# SCH_EsquematicoCorregido_Final.net
KiCad netlist of a schematic drawn in EasyEDA
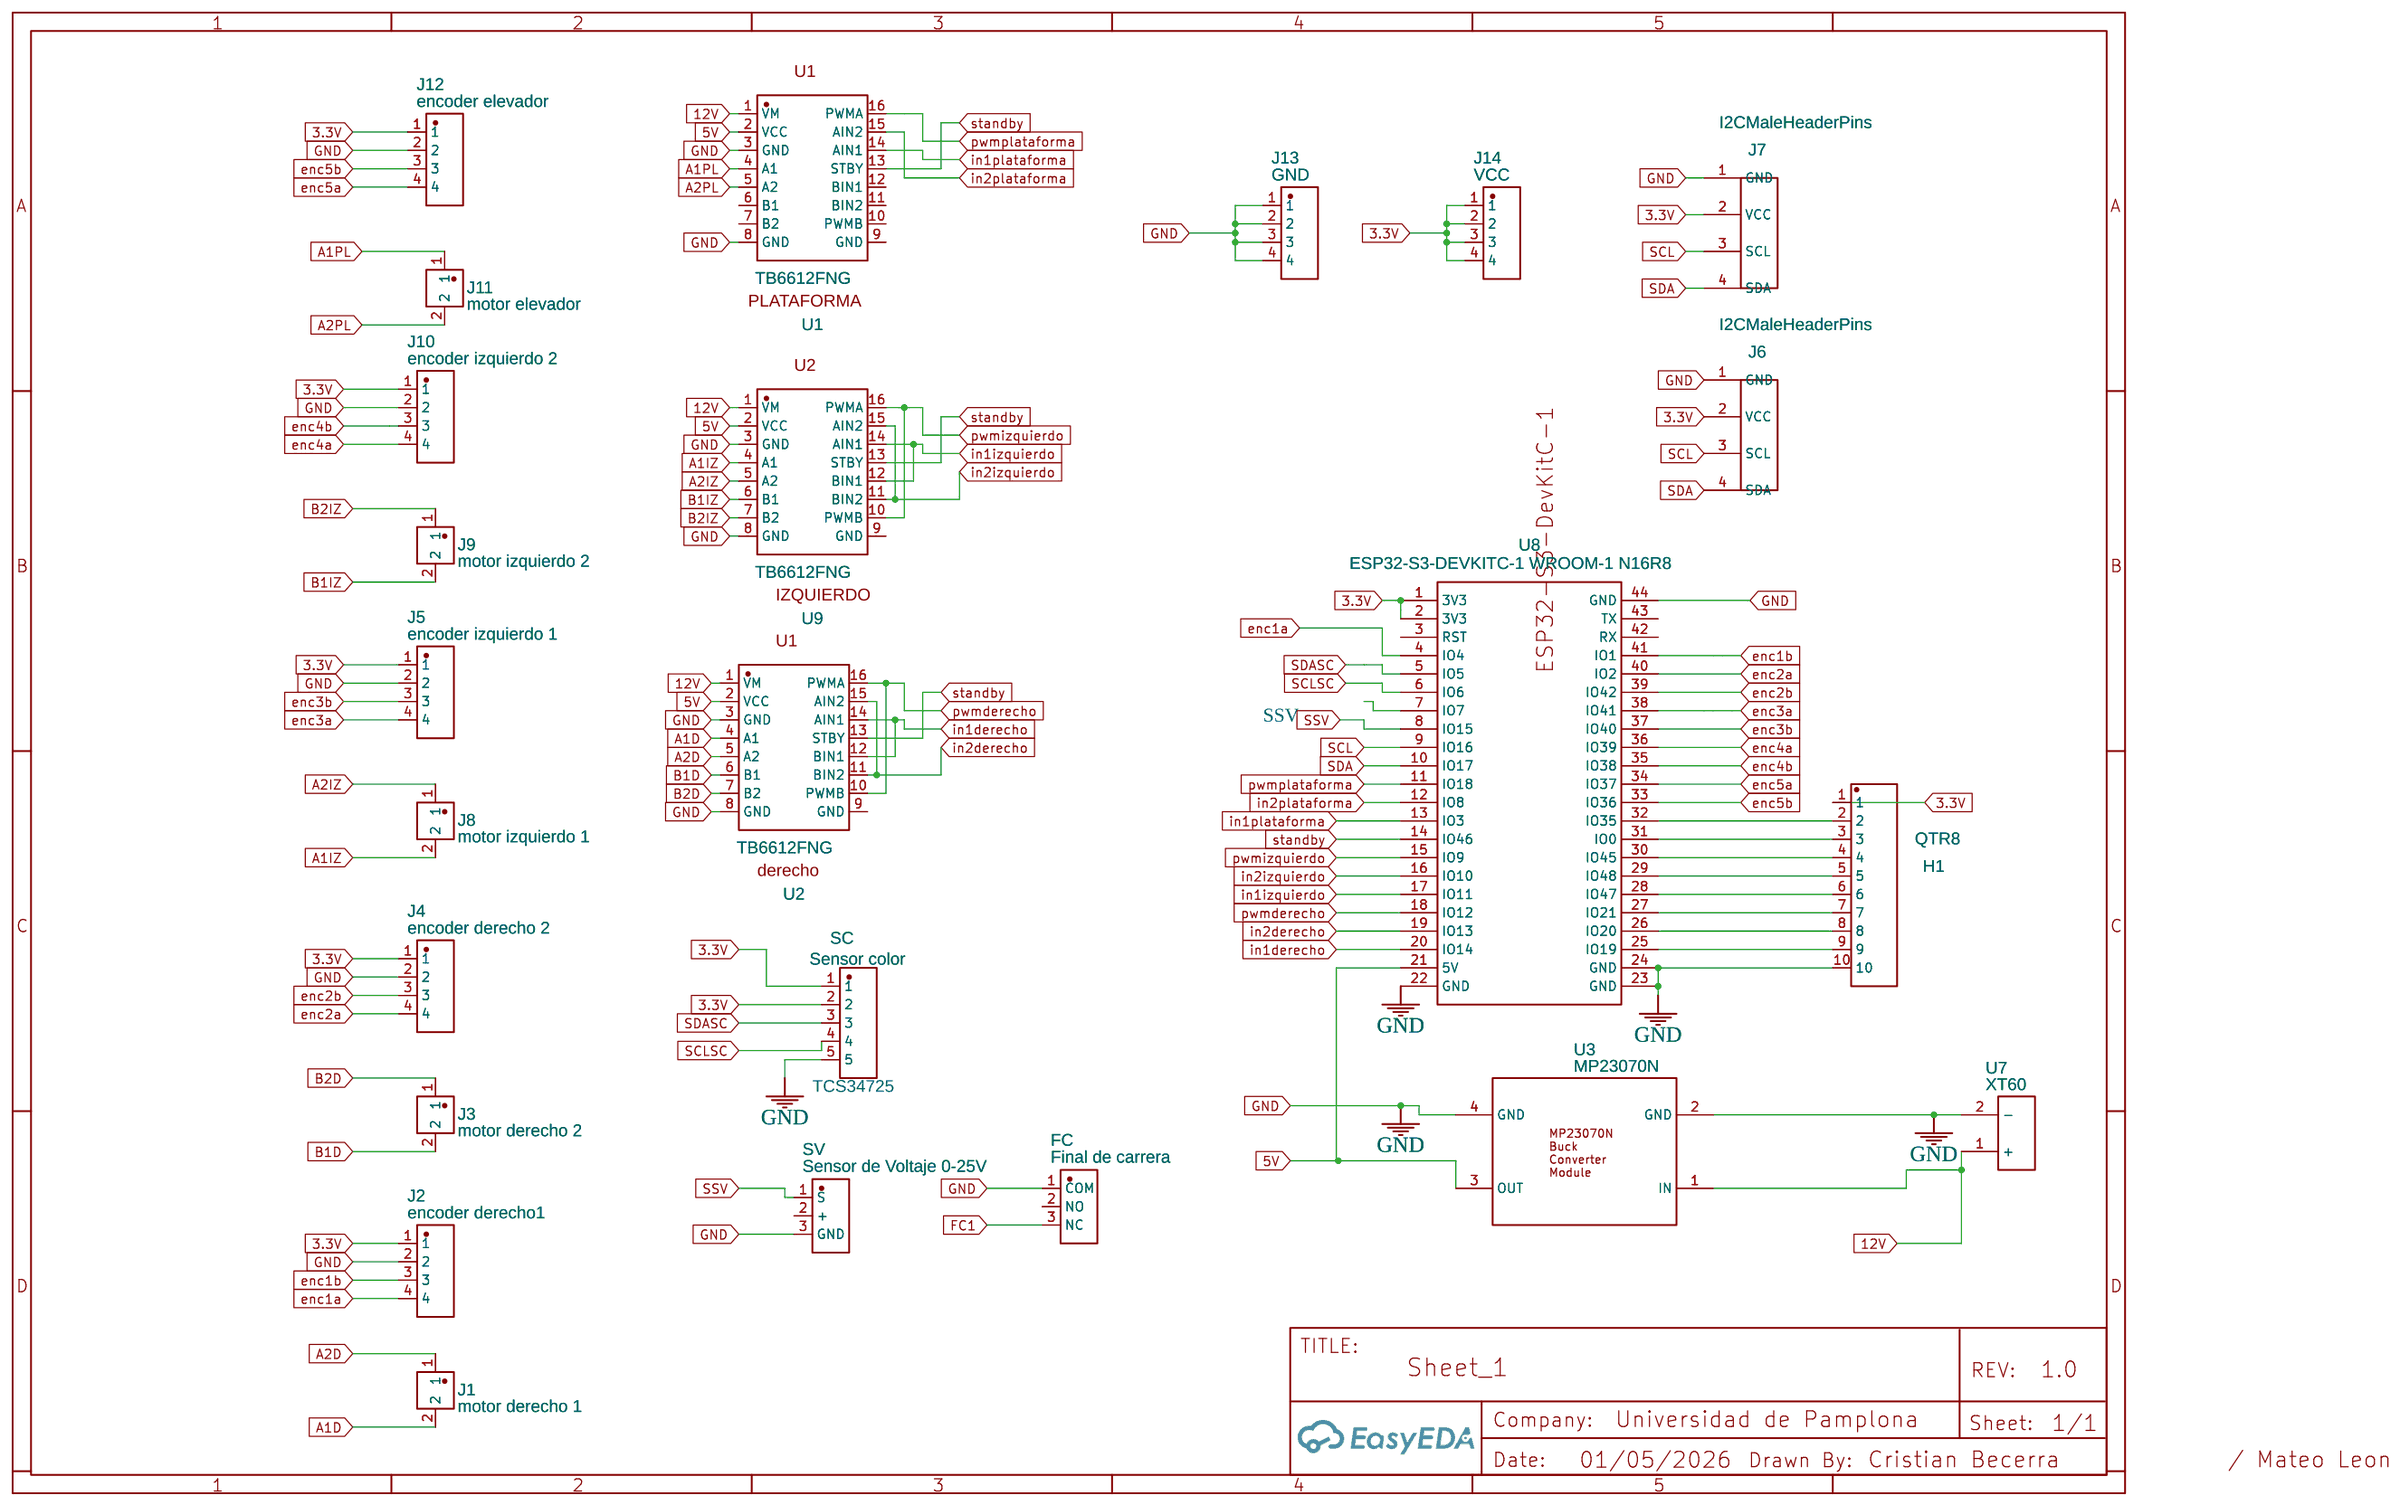
[diagram p0: schematic sheet]

(export (version "E")
  (design (tool "Eeschema 10.0.6"))
  (components
    (comp (ref "FC")
      (value "Final de carrera")
      (fields
        (field (name "Manufacturer Part") "5557WRF-1X3P(HDGC4201WR-F-1X3P)")
        (field (name "Manufacturer") "HDGC(华德共创)")
      )
      (libsource (lib "") (part "5557WRF-1X3P(HDGC4201WR-F-1X3P)"))
    )
    (comp (ref "H1")
      (value "QTR8")
      (fields (field (name "Manufacturer Part") "2.54-1*10P针") (field (name "Manufacturer") "BOOMELE(博穆精密)"))
      (libsource (lib "") (part "Header-Male-2.54_1x10"))
    )
    (comp (ref "J1")
      (value "motor derecho 1")
      (fields (field (name "Manufacturer Part") "2.54*2P-P=2.54mm"))
      (libsource (lib "") (part "2.54*2P-P=2.54MM"))
    )
    (comp (ref "J2")
      (value "encoder derecho1")
      (fields (field (name "Manufacturer Part") "38001334") (field (name "Manufacturer") "MOLEX"))
      (libsource (lib "") (part "38001334"))
    )
    (comp (ref "J3")
      (value "motor derecho 2")
      (fields (field (name "Manufacturer Part") "2.54*2P-P=2.54mm"))
      (libsource (lib "") (part "2.54*2P-P=2.54MM"))
    )
    (comp (ref "J4")
      (value "encoder derecho 2")
      (fields (field (name "Manufacturer Part") "38001334") (field (name "Manufacturer") "MOLEX"))
      (libsource (lib "") (part "38001334"))
    )
    (comp (ref "J5")
      (value "encoder izquierdo 1")
      (fields (field (name "Manufacturer Part") "38001334") (field (name "Manufacturer") "MOLEX"))
      (libsource (lib "") (part "38001334"))
    )
    (comp (ref "J6") (value "I2CMaleHeaderPins") (libsource (lib "") (part "I2CMaleHeaderPins")))
    (comp (ref "J7") (value "I2CMaleHeaderPins") (libsource (lib "") (part "I2CMaleHeaderPins")))
    (comp (ref "J8")
      (value "motor izquierdo 1")
      (fields (field (name "Manufacturer Part") "2.54*2P-P=2.54mm"))
      (libsource (lib "") (part "2.54*2P-P=2.54MM"))
    )
    (comp (ref "J9")
      (value "motor izquierdo 2")
      (fields (field (name "Manufacturer Part") "2.54*2P-P=2.54mm"))
      (libsource (lib "") (part "2.54*2P-P=2.54MM"))
    )
    (comp (ref "J10")
      (value "encoder izquierdo 2")
      (fields (field (name "Manufacturer Part") "38001334") (field (name "Manufacturer") "MOLEX"))
      (libsource (lib "") (part "38001334"))
    )
    (comp (ref "J11")
      (value "motor elevador")
      (fields (field (name "Manufacturer Part") "2.54*2P-P=2.54mm"))
      (libsource (lib "") (part "2.54*2P-P=2.54MM"))
    )
    (comp (ref "J12")
      (value "encoder elevador")
      (fields (field (name "Manufacturer Part") "38001334") (field (name "Manufacturer") "MOLEX"))
      (libsource (lib "") (part "38001334"))
    )
    (comp (ref "J13")
      (value "GND")
      (fields (field (name "Manufacturer Part") "38001334") (field (name "Manufacturer") "MOLEX"))
      (libsource (lib "") (part "38001334"))
    )
    (comp (ref "J14")
      (value "VCC")
      (fields (field (name "Manufacturer Part") "38001334") (field (name "Manufacturer") "MOLEX"))
      (libsource (lib "") (part "38001334"))
    )
    (comp (ref "SC")
      (value "Sensor color")
      (fields
        (field (name "Manufacturer Part") "5557WR-1X5P(HDGC4201WR-1X5P)")
        (field (name "Manufacturer") "HDGC(华德共创)")
      )
      (libsource (lib "") (part "5557WR-1X5P(HDGC4201WR-1X5P)"))
    )
    (comp (ref "SV")
      (value "Sensor de Voltaje 0-25V")
      (fields
        (field (name "Manufacturer Part") "5557WRF-1X3P(HDGC4201WR-F-1X3P)")
        (field (name "Manufacturer") "HDGC(华德共创)")
      )
      (libsource (lib "") (part "5557WRF-1X3P(HDGC4201WR-F-1X3P)_1"))
    )
    (comp (ref "U1") (value "TB6612FNG") (libsource (lib "") (part "TB6612FNG SPARKFUN_1")))
    (comp (ref "U2") (value "TB6612FNG") (libsource (lib "") (part "TB6612FNG SPARKFUN_2")))
    (comp (ref "U3")
      (value "MP23070N")
      (fields (field (name "Manufacturer Part") "MP23070N Buck Converter Module"))
      (libsource (lib "") (part "MP23070N BUCK CONVERTER MODULE"))
    )
    (comp (ref "U7") (value "XT60") (libsource (lib "") (part "XT60")))
    (comp (ref "U8")
      (value "ESP32-S3-DEVKITC-1 WROOM-1 N16R8")
      (fields (field (name "Manufacturer") "Espressif"))
      (libsource (lib "") (part "ESP32-S3-DEVKITC-1 WROOM-1 N16R8"))
    )
    (comp (ref "U9") (value "TB6612FNG") (libsource (lib "") (part "TB6612FNG SPARKFUN")))
  )
  (nets
    (net (code "1") (name "3.3V") (class "Default")
      (node (ref "H1") (pin "1") (pinfunction "1_1") (pintype "unspecified"))
      (node (ref "J10") (pin "1") (pinfunction "1_1") (pintype "unspecified"))
      (node (ref "J12") (pin "1") (pinfunction "1_1") (pintype "unspecified"))
      (node (ref "J14") (pin "1") (pinfunction "1_1") (pintype "unspecified"))
      (node (ref "J14") (pin "2") (pinfunction "2_2") (pintype "unspecified"))
      (node (ref "J14") (pin "3") (pinfunction "3_3") (pintype "unspecified"))
      (node (ref "J14") (pin "4") (pinfunction "4_4") (pintype "unspecified"))
      (node (ref "J2") (pin "1") (pinfunction "1_1") (pintype "unspecified"))
      (node (ref "J4") (pin "1") (pinfunction "1_1") (pintype "unspecified"))
      (node (ref "J5") (pin "1") (pinfunction "1_1") (pintype "unspecified"))
      (node (ref "J6") (pin "2") (pinfunction "VCC_2") (pintype "unspecified"))
      (node (ref "J7") (pin "2") (pinfunction "VCC_2") (pintype "unspecified"))
      (node (ref "SC") (pin "1") (pinfunction "1_1") (pintype "unspecified"))
      (node (ref "SC") (pin "2") (pinfunction "2_2") (pintype "unspecified"))
      (node (ref "U8") (pin "1") (pinfunction "3V3_1") (pintype "unspecified"))
      (node (ref "U8") (pin "2") (pinfunction "3V3_2") (pintype "unspecified"))
    )
    (net (code "2") (name "5V") (class "Default")
      (node (ref "U1") (pin "2") (pinfunction "VCC_2") (pintype "unspecified"))
      (node (ref "U2") (pin "2") (pinfunction "VCC_2") (pintype "unspecified"))
      (node (ref "U3") (pin "3") (pinfunction "OUT_3") (pintype "unspecified"))
      (node (ref "U8") (pin "21") (pinfunction "5V_21") (pintype "unspecified"))
      (node (ref "U9") (pin "2") (pinfunction "VCC_2") (pintype "unspecified"))
    )
    (net (code "3") (name "12V") (class "Default")
      (node (ref "U1") (pin "1") (pinfunction "VM_1") (pintype "unspecified"))
      (node (ref "U2") (pin "1") (pinfunction "VM_1") (pintype "unspecified"))
      (node (ref "U3") (pin "1") (pinfunction "IN_1") (pintype "unspecified"))
      (node (ref "U7") (pin "1") (pinfunction "+_1") (pintype "unspecified"))
      (node (ref "U9") (pin "1") (pinfunction "VM_1") (pintype "unspecified"))
    )
    (net (code "4") (name "A1D") (class "Default")
      (node (ref "J1") (pin "2") (pinfunction "2_2") (pintype "unspecified"))
      (node (ref "U2") (pin "4") (pinfunction "A1_4") (pintype "unspecified"))
    )
    (net (code "5") (name "A1IZ") (class "Default")
      (node (ref "J8") (pin "2") (pinfunction "2_2") (pintype "unspecified"))
      (node (ref "U9") (pin "4") (pinfunction "A1_4") (pintype "unspecified"))
    )
    (net (code "6") (name "A1PL") (class "Default")
      (node (ref "J11") (pin "1") (pinfunction "1_1") (pintype "unspecified"))
      (node (ref "U1") (pin "4") (pinfunction "A1_4") (pintype "unspecified"))
    )
    (net (code "7") (name "A2D") (class "Default")
      (node (ref "J1") (pin "1") (pinfunction "1_1") (pintype "unspecified"))
      (node (ref "U2") (pin "5") (pinfunction "A2_5") (pintype "unspecified"))
    )
    (net (code "8") (name "A2IZ") (class "Default")
      (node (ref "J8") (pin "1") (pinfunction "1_1") (pintype "unspecified"))
      (node (ref "U9") (pin "5") (pinfunction "A2_5") (pintype "unspecified"))
    )
    (net (code "9") (name "A2PL") (class "Default")
      (node (ref "J11") (pin "2") (pinfunction "2_2") (pintype "unspecified"))
      (node (ref "U1") (pin "5") (pinfunction "A2_5") (pintype "unspecified"))
    )
    (net (code "10") (name "B1D") (class "Default")
      (node (ref "J3") (pin "2") (pinfunction "2_2") (pintype "unspecified"))
      (node (ref "U2") (pin "6") (pinfunction "B1_6") (pintype "unspecified"))
    )
    (net (code "11") (name "B1IZ") (class "Default")
      (node (ref "J9") (pin "2") (pinfunction "2_2") (pintype "unspecified"))
      (node (ref "U9") (pin "6") (pinfunction "B1_6") (pintype "unspecified"))
    )
    (net (code "12") (name "B2D") (class "Default")
      (node (ref "J3") (pin "1") (pinfunction "1_1") (pintype "unspecified"))
      (node (ref "U2") (pin "7") (pinfunction "B2_7") (pintype "unspecified"))
    )
    (net (code "13") (name "B2IZ") (class "Default")
      (node (ref "J9") (pin "1") (pinfunction "1_1") (pintype "unspecified"))
      (node (ref "U9") (pin "7") (pinfunction "B2_7") (pintype "unspecified"))
    )
    (net (code "14") (name "FC1") (class "Default")
      (node (ref "FC") (pin "3") (pinfunction "NC_3") (pintype "unspecified"))
    )
    (net (code "15") (name "GND") (class "Default")
      (node (ref "FC") (pin "1") (pinfunction "COM_1") (pintype "unspecified"))
      (node (ref "H1") (pin "10") (pinfunction "10_10") (pintype "unspecified"))
      (node (ref "J10") (pin "2") (pinfunction "2_2") (pintype "unspecified"))
      (node (ref "J12") (pin "2") (pinfunction "2_2") (pintype "unspecified"))
      (node (ref "J13") (pin "1") (pinfunction "1_1") (pintype "unspecified"))
      (node (ref "J13") (pin "2") (pinfunction "2_2") (pintype "unspecified"))
      (node (ref "J13") (pin "3") (pinfunction "3_3") (pintype "unspecified"))
      (node (ref "J13") (pin "4") (pinfunction "4_4") (pintype "unspecified"))
      (node (ref "J2") (pin "2") (pinfunction "2_2") (pintype "unspecified"))
      (node (ref "J4") (pin "2") (pinfunction "2_2") (pintype "unspecified"))
      (node (ref "J5") (pin "2") (pinfunction "2_2") (pintype "unspecified"))
      (node (ref "J6") (pin "1") (pinfunction "GND_1") (pintype "unspecified"))
      (node (ref "J7") (pin "1") (pinfunction "GND_1") (pintype "unspecified"))
      (node (ref "SC") (pin "5") (pinfunction "5_5") (pintype "unspecified"))
      (node (ref "SV") (pin "3") (pinfunction "GND_3") (pintype "unspecified"))
      (node (ref "U1") (pin "3") (pinfunction "GND_3") (pintype "unspecified"))
      (node (ref "U1") (pin "8") (pinfunction "GND_8") (pintype "unspecified"))
      (node (ref "U2") (pin "3") (pinfunction "GND_3") (pintype "unspecified"))
      (node (ref "U2") (pin "8") (pinfunction "GND_8") (pintype "unspecified"))
      (node (ref "U3") (pin "2") (pinfunction "GND_2") (pintype "unspecified"))
      (node (ref "U3") (pin "4") (pinfunction "GND_4") (pintype "unspecified"))
      (node (ref "U7") (pin "2") (pinfunction "-_2") (pintype "unspecified"))
      (node (ref "U8") (pin "22") (pinfunction "GND_22") (pintype "unspecified"))
      (node (ref "U8") (pin "23") (pinfunction "GND_23") (pintype "unspecified"))
      (node (ref "U8") (pin "24") (pinfunction "GND_24") (pintype "unspecified"))
      (node (ref "U8") (pin "44") (pinfunction "GND_44") (pintype "unspecified"))
      (node (ref "U9") (pin "3") (pinfunction "GND_3") (pintype "unspecified"))
      (node (ref "U9") (pin "8") (pinfunction "GND_8") (pintype "unspecified"))
    )
    (net (code "16") (name "Net-(U8-IO0)") (class "Default")
      (node (ref "H1") (pin "3") (pinfunction "3_3") (pintype "unspecified"))
      (node (ref "U8") (pin "31") (pinfunction "IO0_31") (pintype "unspecified"))
    )
    (net (code "17") (name "Net-(U8-IO19)") (class "Default")
      (node (ref "H1") (pin "9") (pinfunction "9_9") (pintype "unspecified"))
      (node (ref "U8") (pin "25") (pinfunction "IO19_25") (pintype "unspecified"))
    )
    (net (code "18") (name "Net-(U8-IO20)") (class "Default")
      (node (ref "H1") (pin "8") (pinfunction "8_8") (pintype "unspecified"))
      (node (ref "U8") (pin "26") (pinfunction "IO20_26") (pintype "unspecified"))
    )
    (net (code "19") (name "Net-(U8-IO21)") (class "Default")
      (node (ref "H1") (pin "7") (pinfunction "7_7") (pintype "unspecified"))
      (node (ref "U8") (pin "27") (pinfunction "IO21_27") (pintype "unspecified"))
    )
    (net (code "20") (name "Net-(U8-IO35)") (class "Default")
      (node (ref "H1") (pin "2") (pinfunction "2_2") (pintype "unspecified"))
      (node (ref "U8") (pin "32") (pinfunction "IO35_32") (pintype "unspecified"))
    )
    (net (code "21") (name "Net-(U8-IO45)") (class "Default")
      (node (ref "H1") (pin "4") (pinfunction "4_4") (pintype "unspecified"))
      (node (ref "U8") (pin "30") (pinfunction "IO45_30") (pintype "unspecified"))
    )
    (net (code "22") (name "Net-(U8-IO47)") (class "Default")
      (node (ref "H1") (pin "6") (pinfunction "6_6") (pintype "unspecified"))
      (node (ref "U8") (pin "28") (pinfunction "IO47_28") (pintype "unspecified"))
    )
    (net (code "23") (name "Net-(U8-IO48)") (class "Default")
      (node (ref "H1") (pin "5") (pinfunction "5_5") (pintype "unspecified"))
      (node (ref "U8") (pin "29") (pinfunction "IO48_29") (pintype "unspecified"))
    )
    (net (code "24") (name "SCL") (class "Default")
      (node (ref "J6") (pin "3") (pinfunction "SCL_3") (pintype "unspecified"))
      (node (ref "J7") (pin "3") (pinfunction "SCL_3") (pintype "unspecified"))
      (node (ref "U8") (pin "9") (pinfunction "IO16_9") (pintype "unspecified"))
    )
    (net (code "25") (name "SCLSC") (class "Default")
      (node (ref "SC") (pin "4") (pinfunction "4_4") (pintype "unspecified"))
      (node (ref "U8") (pin "6") (pinfunction "IO6_6") (pintype "unspecified"))
    )
    (net (code "26") (name "SDA") (class "Default")
      (node (ref "J6") (pin "4") (pinfunction "SDA_4") (pintype "unspecified"))
      (node (ref "J7") (pin "4") (pinfunction "SDA_4") (pintype "unspecified"))
      (node (ref "U8") (pin "10") (pinfunction "IO17_10") (pintype "unspecified"))
    )
    (net (code "27") (name "SDASC") (class "Default")
      (node (ref "SC") (pin "3") (pinfunction "3_3") (pintype "unspecified"))
      (node (ref "U8") (pin "5") (pinfunction "IO5_5") (pintype "unspecified"))
    )
    (net (code "28") (name "SSV") (class "Default")
      (node (ref "SV") (pin "1") (pinfunction "S_1") (pintype "unspecified"))
      (node (ref "U8") (pin "8") (pinfunction "IO15_8") (pintype "unspecified"))
    )
    (net (code "29") (name "enc1a") (class "Default")
      (node (ref "J2") (pin "4") (pinfunction "4_4") (pintype "unspecified"))
      (node (ref "U8") (pin "4") (pinfunction "IO4_4") (pintype "unspecified"))
    )
    (net (code "30") (name "enc1b") (class "Default")
      (node (ref "J2") (pin "3") (pinfunction "3_3") (pintype "unspecified"))
      (node (ref "U8") (pin "41") (pinfunction "IO1_41") (pintype "unspecified"))
    )
    (net (code "31") (name "enc2a") (class "Default")
      (node (ref "J4") (pin "4") (pinfunction "4_4") (pintype "unspecified"))
      (node (ref "U8") (pin "40") (pinfunction "IO2_40") (pintype "unspecified"))
    )
    (net (code "32") (name "enc2b") (class "Default")
      (node (ref "J4") (pin "3") (pinfunction "3_3") (pintype "unspecified"))
      (node (ref "U8") (pin "39") (pinfunction "IO42_39") (pintype "unspecified"))
    )
    (net (code "33") (name "enc3a") (class "Default")
      (node (ref "J5") (pin "4") (pinfunction "4_4") (pintype "unspecified"))
      (node (ref "U8") (pin "38") (pinfunction "IO41_38") (pintype "unspecified"))
    )
    (net (code "34") (name "enc3b") (class "Default")
      (node (ref "J5") (pin "3") (pinfunction "3_3") (pintype "unspecified"))
      (node (ref "U8") (pin "37") (pinfunction "IO40_37") (pintype "unspecified"))
    )
    (net (code "35") (name "enc4a") (class "Default")
      (node (ref "J10") (pin "4") (pinfunction "4_4") (pintype "unspecified"))
      (node (ref "U8") (pin "36") (pinfunction "IO39_36") (pintype "unspecified"))
    )
    (net (code "36") (name "enc4b") (class "Default")
      (node (ref "J10") (pin "3") (pinfunction "3_3") (pintype "unspecified"))
      (node (ref "U8") (pin "35") (pinfunction "IO38_35") (pintype "unspecified"))
    )
    (net (code "37") (name "enc5a") (class "Default")
      (node (ref "J12") (pin "4") (pinfunction "4_4") (pintype "unspecified"))
      (node (ref "U8") (pin "34") (pinfunction "IO37_34") (pintype "unspecified"))
    )
    (net (code "38") (name "enc5b") (class "Default")
      (node (ref "J12") (pin "3") (pinfunction "3_3") (pintype "unspecified"))
      (node (ref "U8") (pin "33") (pinfunction "IO36_33") (pintype "unspecified"))
    )
    (net (code "39") (name "in1derecho") (class "Default")
      (node (ref "U2") (pin "12") (pinfunction "BIN1_12") (pintype "unspecified"))
      (node (ref "U2") (pin "14") (pinfunction "AIN1_14") (pintype "unspecified"))
      (node (ref "U8") (pin "20") (pinfunction "IO14_20") (pintype "unspecified"))
    )
    (net (code "40") (name "in1izquierdo") (class "Default")
      (node (ref "U8") (pin "17") (pinfunction "IO11_17") (pintype "unspecified"))
      (node (ref "U9") (pin "12") (pinfunction "BIN1_12") (pintype "unspecified"))
      (node (ref "U9") (pin "14") (pinfunction "AIN1_14") (pintype "unspecified"))
    )
    (net (code "41") (name "in1plataforma") (class "Default")
      (node (ref "U1") (pin "14") (pinfunction "AIN1_14") (pintype "unspecified"))
      (node (ref "U8") (pin "13") (pinfunction "IO3_13") (pintype "unspecified"))
    )
    (net (code "42") (name "in2derecho") (class "Default")
      (node (ref "U2") (pin "11") (pinfunction "BIN2_11") (pintype "unspecified"))
      (node (ref "U2") (pin "15") (pinfunction "AIN2_15") (pintype "unspecified"))
      (node (ref "U8") (pin "19") (pinfunction "IO13_19") (pintype "unspecified"))
    )
    (net (code "43") (name "in2izquierdo") (class "Default")
      (node (ref "U8") (pin "16") (pinfunction "IO10_16") (pintype "unspecified"))
      (node (ref "U9") (pin "11") (pinfunction "BIN2_11") (pintype "unspecified"))
      (node (ref "U9") (pin "15") (pinfunction "AIN2_15") (pintype "unspecified"))
    )
    (net (code "44") (name "in2plataforma") (class "Default")
      (node (ref "U1") (pin "15") (pinfunction "AIN2_15") (pintype "unspecified"))
      (node (ref "U8") (pin "12") (pinfunction "IO8_12") (pintype "unspecified"))
    )
    (net (code "45") (name "pwmderecho") (class "Default")
      (node (ref "U2") (pin "10") (pinfunction "PWMB_10") (pintype "unspecified"))
      (node (ref "U2") (pin "16") (pinfunction "PWMA_16") (pintype "unspecified"))
      (node (ref "U8") (pin "18") (pinfunction "IO12_18") (pintype "unspecified"))
    )
    (net (code "46") (name "pwmizquierdo") (class "Default")
      (node (ref "U8") (pin "15") (pinfunction "IO9_15") (pintype "unspecified"))
      (node (ref "U9") (pin "10") (pinfunction "PWMB_10") (pintype "unspecified"))
      (node (ref "U9") (pin "16") (pinfunction "PWMA_16") (pintype "unspecified"))
    )
    (net (code "47") (name "pwmplataforma") (class "Default")
      (node (ref "U1") (pin "16") (pinfunction "PWMA_16") (pintype "unspecified"))
      (node (ref "U8") (pin "11") (pinfunction "IO18_11") (pintype "unspecified"))
    )
    (net (code "48") (name "standby") (class "Default")
      (node (ref "U1") (pin "13") (pinfunction "STBY_13") (pintype "unspecified"))
      (node (ref "U2") (pin "13") (pinfunction "STBY_13") (pintype "unspecified"))
      (node (ref "U8") (pin "14") (pinfunction "IO46_14") (pintype "unspecified"))
      (node (ref "U9") (pin "13") (pinfunction "STBY_13") (pintype "unspecified"))
    )
    (net (code "49") (name "unconnected-(FC-NO-Pad2)") (class "Default")
      (node (ref "FC") (pin "2") (pinfunction "NO_2") (pintype "unspecified"))
    )
    (net (code "50") (name "unconnected-(SV-+-Pad2)") (class "Default")
      (node (ref "SV") (pin "2") (pinfunction "+_2") (pintype "unspecified"))
    )
    (net (code "51") (name "unconnected-(U1-B1-Pad6)") (class "Default")
      (node (ref "U1") (pin "6") (pinfunction "B1_6") (pintype "unspecified"))
    )
    (net (code "52") (name "unconnected-(U1-B2-Pad7)") (class "Default")
      (node (ref "U1") (pin "7") (pinfunction "B2_7") (pintype "unspecified"))
    )
    (net (code "53") (name "unconnected-(U1-BIN1-Pad12)") (class "Default")
      (node (ref "U1") (pin "12") (pinfunction "BIN1_12") (pintype "unspecified"))
    )
    (net (code "54") (name "unconnected-(U1-BIN2-Pad11)") (class "Default")
      (node (ref "U1") (pin "11") (pinfunction "BIN2_11") (pintype "unspecified"))
    )
    (net (code "55") (name "unconnected-(U1-GND-Pad9)") (class "Default")
      (node (ref "U1") (pin "9") (pinfunction "GND_9") (pintype "unspecified"))
    )
    (net (code "56") (name "unconnected-(U1-PWMB-Pad10)") (class "Default")
      (node (ref "U1") (pin "10") (pinfunction "PWMB_10") (pintype "unspecified"))
    )
    (net (code "57") (name "unconnected-(U2-GND-Pad9)") (class "Default")
      (node (ref "U2") (pin "9") (pinfunction "GND_9") (pintype "unspecified"))
    )
    (net (code "58") (name "unconnected-(U8-IO7-Pad7)") (class "Default")
      (node (ref "U8") (pin "7") (pinfunction "IO7_7") (pintype "unspecified"))
    )
    (net (code "59") (name "unconnected-(U8-RST-Pad3)") (class "Default")
      (node (ref "U8") (pin "3") (pinfunction "RST_3") (pintype "unspecified"))
    )
    (net (code "60") (name "unconnected-(U8-RX-Pad42)") (class "Default")
      (node (ref "U8") (pin "42") (pinfunction "RX_42") (pintype "unspecified"))
    )
    (net (code "61") (name "unconnected-(U8-TX-Pad43)") (class "Default")
      (node (ref "U8") (pin "43") (pinfunction "TX_43") (pintype "unspecified"))
    )
    (net (code "62") (name "unconnected-(U9-GND-Pad9)") (class "Default")
      (node (ref "U9") (pin "9") (pinfunction "GND_9") (pintype "unspecified"))
    )
  )
)
